# 17_FPGA_B12_B13_B14_B15.net
KiCad netlist of a schematic drawn in Altium Designer
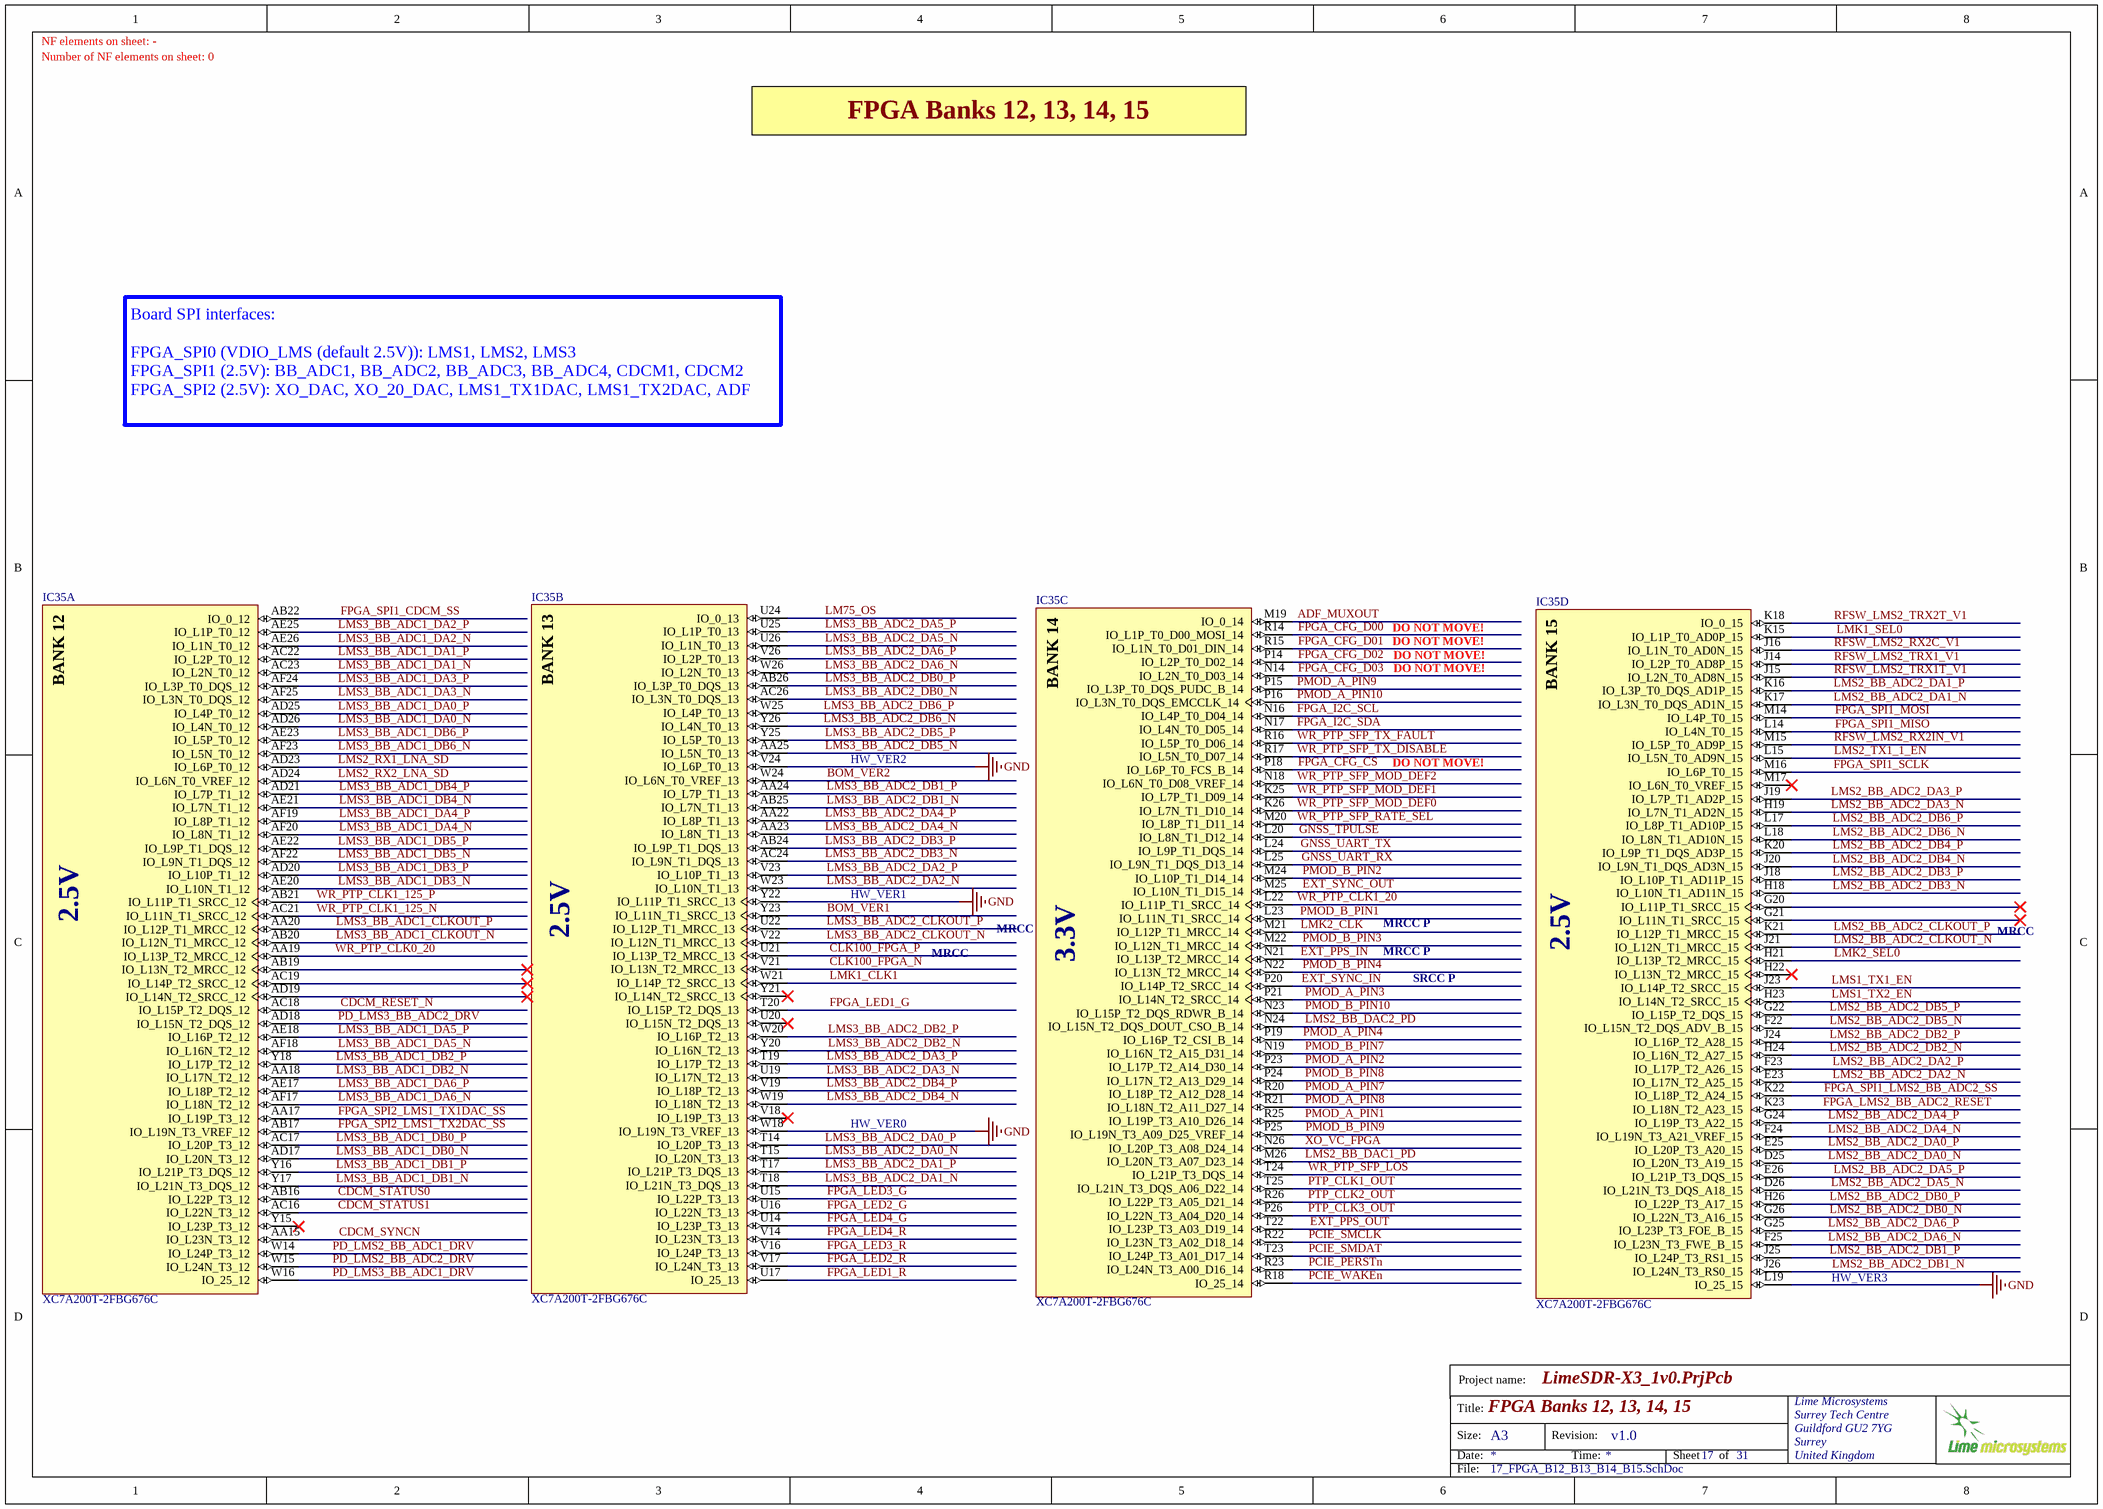
[diagram p0: 17_FPGA_B12_B13_B14_B15.SchDoc]

(export (version "E")
  (design (tool "Eeschema 10.0.6"))
  (components
    (comp (ref "IC35")
      (value "XC7A200T-2FBG676C")
      (footprint "XC7A200T-2FBG676C_FBG676")
      (description "Artix-7 FPGA, 400 User I/Os, 8 GTP, 676-Ball BGA, Speed Grade 2, Commercial Grade, Pb-Free")
      (fields (field (name "MANUFACTURER") "Xilinx"))
      (libsource (lib "") (part "XC7A200T-2FBG676C_2"))
    )
  )
  (nets
    (net (code "1") (name "/ADF_MUXOUT") (class "Default")
      (node (ref "IC35") (pin "M19") (pinfunction "IO_0_14_M19") (pintype "bidirectional"))
    )
    (net (code "2") (name "/BOM_VER1") (class "Default")
      (node (ref "IC35") (pin "Y23") (pinfunction "IO_L11N_T1_SRCC_13_Y23") (pintype "bidirectional"))
    )
    (net (code "3") (name "/BOM_VER2") (class "Default")
      (node (ref "IC35") (pin "W24") (pinfunction "IO_L6N_T0_VREF_13_W24") (pintype "bidirectional"))
    )
    (net (code "4") (name "/CDCM_RESET_N") (class "Default")
      (node (ref "IC35") (pin "AC18") (pinfunction "IO_L15P_T2_DQS_12_AC18") (pintype "bidirectional"))
    )
    (net (code "5") (name "/CDCM_STATUS0") (class "Default")
      (node (ref "IC35") (pin "AB16") (pinfunction "IO_L22P_T3_12_AB16") (pintype "bidirectional"))
    )
    (net (code "6") (name "/CDCM_STATUS1") (class "Default")
      (node (ref "IC35") (pin "AC16") (pinfunction "IO_L22N_T3_12_AC16") (pintype "bidirectional"))
    )
    (net (code "7") (name "/CDCM_SYNCN") (class "Default")
      (node (ref "IC35") (pin "AA15") (pinfunction "IO_L23N_T3_12_AA15") (pintype "bidirectional"))
    )
    (net (code "8") (name "/CLK100_FPGA_N") (class "Default")
      (node (ref "IC35") (pin "V21") (pinfunction "IO_L13N_T2_MRCC_13_V21") (pintype "bidirectional"))
    )
    (net (code "9") (name "/CLK100_FPGA_P") (class "Default")
      (node (ref "IC35") (pin "U21") (pinfunction "IO_L13P_T2_MRCC_13_U21") (pintype "bidirectional"))
    )
    (net (code "10") (name "/EXT_PPS_IN") (class "Default")
      (node (ref "IC35") (pin "N21") (pinfunction "IO_L13P_T2_MRCC_14_N21") (pintype "bidirectional"))
    )
    (net (code "11") (name "/EXT_PPS_OUT") (class "Default")
      (node (ref "IC35") (pin "T22") (pinfunction "IO_L23P_T3_A03_D19_14_T22") (pintype "bidirectional"))
    )
    (net (code "12") (name "/EXT_SYNC_IN") (class "Default")
      (node (ref "IC35") (pin "P20") (pinfunction "IO_L14P_T2_SRCC_14_P20") (pintype "bidirectional"))
    )
    (net (code "13") (name "/EXT_SYNC_OUT") (class "Default")
      (node (ref "IC35") (pin "M25") (pinfunction "IO_L10N_T1_D15_14_M25") (pintype "bidirectional"))
    )
    (net (code "14") (name "/FPGA_CFG_CS") (class "Default")
      (node (ref "IC35") (pin "P18") (pinfunction "IO_L6P_T0_FCS_B_14_P18") (pintype "bidirectional"))
    )
    (net (code "15") (name "/FPGA_CFG_D00") (class "Default")
      (node (ref "IC35") (pin "R14") (pinfunction "IO_L1P_T0_D00_MOSI_14_R14") (pintype "bidirectional"))
    )
    (net (code "16") (name "/FPGA_CFG_D01") (class "Default")
      (node (ref "IC35") (pin "R15") (pinfunction "IO_L1N_T0_D01_DIN_14_R15") (pintype "bidirectional"))
    )
    (net (code "17") (name "/FPGA_CFG_D02") (class "Default")
      (node (ref "IC35") (pin "P14") (pinfunction "IO_L2P_T0_D02_14_P14") (pintype "bidirectional"))
    )
    (net (code "18") (name "/FPGA_CFG_D03") (class "Default")
      (node (ref "IC35") (pin "N14") (pinfunction "IO_L2N_T0_D03_14_N14") (pintype "bidirectional"))
    )
    (net (code "19") (name "/FPGA_I2C_SCL") (class "Default")
      (node (ref "IC35") (pin "N16") (pinfunction "IO_L4P_T0_D04_14_N16") (pintype "bidirectional"))
    )
    (net (code "20") (name "/FPGA_I2C_SDA") (class "Default")
      (node (ref "IC35") (pin "N17") (pinfunction "IO_L4N_T0_D05_14_N17") (pintype "bidirectional"))
    )
    (net (code "21") (name "/FPGA_LED1_G") (class "Default")
      (node (ref "IC35") (pin "T20") (pinfunction "IO_L15P_T2_DQS_13_T20") (pintype "bidirectional"))
    )
    (net (code "22") (name "/FPGA_LED1_R") (class "Default")
      (node (ref "IC35") (pin "U17") (pinfunction "IO_25_13_U17") (pintype "bidirectional"))
    )
    (net (code "23") (name "/FPGA_LED2_G") (class "Default")
      (node (ref "IC35") (pin "U16") (pinfunction "IO_L22N_T3_13_U16") (pintype "bidirectional"))
    )
    (net (code "24") (name "/FPGA_LED2_R") (class "Default")
      (node (ref "IC35") (pin "V17") (pinfunction "IO_L24N_T3_13_V17") (pintype "bidirectional"))
    )
    (net (code "25") (name "/FPGA_LED3_G") (class "Default")
      (node (ref "IC35") (pin "U15") (pinfunction "IO_L22P_T3_13_U15") (pintype "bidirectional"))
    )
    (net (code "26") (name "/FPGA_LED3_R") (class "Default")
      (node (ref "IC35") (pin "V16") (pinfunction "IO_L24P_T3_13_V16") (pintype "bidirectional"))
    )
    (net (code "27") (name "/FPGA_LED4_G") (class "Default")
      (node (ref "IC35") (pin "U14") (pinfunction "IO_L23P_T3_13_U14") (pintype "bidirectional"))
    )
    (net (code "28") (name "/FPGA_LED4_R") (class "Default")
      (node (ref "IC35") (pin "V14") (pinfunction "IO_L23N_T3_13_V14") (pintype "bidirectional"))
    )
    (net (code "29") (name "/FPGA_LMS2_BB_ADC2_RESET") (class "Default")
      (node (ref "IC35") (pin "K23") (pinfunction "IO_L18N_T2_A23_15_K23") (pintype "bidirectional"))
    )
    (net (code "30") (name "/FPGA_SPI1_CDCM_SS") (class "Default")
      (node (ref "IC35") (pin "AB22") (pinfunction "IO_0_12_AB22") (pintype "bidirectional"))
    )
    (net (code "31") (name "/FPGA_SPI1_LMS2_BB_ADC2_SS") (class "Default")
      (node (ref "IC35") (pin "K22") (pinfunction "IO_L18P_T2_A24_15_K22") (pintype "bidirectional"))
    )
    (net (code "32") (name "/FPGA_SPI1_MISO") (class "Default")
      (node (ref "IC35") (pin "L14") (pinfunction "IO_L4N_T0_15_L14") (pintype "bidirectional"))
    )
    (net (code "33") (name "/FPGA_SPI1_MOSI") (class "Default")
      (node (ref "IC35") (pin "M14") (pinfunction "IO_L4P_T0_15_M14") (pintype "bidirectional"))
    )
    (net (code "34") (name "/FPGA_SPI1_SCLK") (class "Default")
      (node (ref "IC35") (pin "M16") (pinfunction "IO_L6P_T0_15_M16") (pintype "bidirectional"))
    )
    (net (code "35") (name "/FPGA_SPI2_LMS1_TX1DAC_SS") (class "Default")
      (node (ref "IC35") (pin "AA17") (pinfunction "IO_L19P_T3_12_AA17") (pintype "bidirectional"))
    )
    (net (code "36") (name "/FPGA_SPI2_LMS1_TX2DAC_SS") (class "Default")
      (node (ref "IC35") (pin "AB17") (pinfunction "IO_L19N_T3_VREF_12_AB17") (pintype "bidirectional"))
    )
    (net (code "37") (name "/GNSS_TPULSE") (class "Default")
      (node (ref "IC35") (pin "L20") (pinfunction "IO_L8N_T1_D12_14_L20") (pintype "bidirectional"))
    )
    (net (code "38") (name "/GNSS_UART_RX") (class "Default")
      (node (ref "IC35") (pin "L25") (pinfunction "IO_L9N_T1_DQS_D13_14_L25") (pintype "bidirectional"))
    )
    (net (code "39") (name "/GNSS_UART_TX") (class "Default")
      (node (ref "IC35") (pin "L24") (pinfunction "IO_L9P_T1_DQS_14_L24") (pintype "bidirectional"))
    )
    (net (code "40") (name "/LM75_OS") (class "Default")
      (node (ref "IC35") (pin "U24") (pinfunction "IO_0_13_U24") (pintype "bidirectional"))
    )
    (net (code "41") (name "/LMK1_CLK1") (class "Default")
      (node (ref "IC35") (pin "W21") (pinfunction "IO_L14P_T2_SRCC_13_W21") (pintype "bidirectional"))
    )
    (net (code "42") (name "/LMK1_SEL0") (class "Default")
      (node (ref "IC35") (pin "K15") (pinfunction "IO_L1P_T0_AD0P_15_K15") (pintype "bidirectional"))
    )
    (net (code "43") (name "/LMK2_CLK") (class "Default")
      (node (ref "IC35") (pin "M21") (pinfunction "IO_L12P_T1_MRCC_14_M21") (pintype "bidirectional"))
    )
    (net (code "44") (name "/LMK2_SEL0") (class "Default")
      (node (ref "IC35") (pin "H21") (pinfunction "IO_L13P_T2_MRCC_15_H21") (pintype "bidirectional"))
    )
    (net (code "45") (name "/LMS1_TX1_EN") (class "Default")
      (node (ref "IC35") (pin "J23") (pinfunction "IO_L14P_T2_SRCC_15_J23") (pintype "bidirectional"))
    )
    (net (code "46") (name "/LMS1_TX2_EN") (class "Default")
      (node (ref "IC35") (pin "H23") (pinfunction "IO_L14N_T2_SRCC_15_H23") (pintype "bidirectional"))
    )
    (net (code "47") (name "/LMS2_BB_ADC2_CLKOUT_N") (class "Default")
      (node (ref "IC35") (pin "J21") (pinfunction "IO_L12N_T1_MRCC_15_J21") (pintype "bidirectional"))
    )
    (net (code "48") (name "/LMS2_BB_ADC2_CLKOUT_P") (class "Default")
      (node (ref "IC35") (pin "K21") (pinfunction "IO_L12P_T1_MRCC_15_K21") (pintype "bidirectional"))
    )
    (net (code "49") (name "/LMS2_BB_ADC2_DA0_N") (class "Default")
      (node (ref "IC35") (pin "D25") (pinfunction "IO_L20N_T3_A19_15_D25") (pintype "bidirectional"))
    )
    (net (code "50") (name "/LMS2_BB_ADC2_DA0_P") (class "Default")
      (node (ref "IC35") (pin "E25") (pinfunction "IO_L20P_T3_A20_15_E25") (pintype "bidirectional"))
    )
    (net (code "51") (name "/LMS2_BB_ADC2_DA1_N") (class "Default")
      (node (ref "IC35") (pin "K17") (pinfunction "IO_L3N_T0_DQS_AD1N_15_K17") (pintype "bidirectional"))
    )
    (net (code "52") (name "/LMS2_BB_ADC2_DA1_P") (class "Default")
      (node (ref "IC35") (pin "K16") (pinfunction "IO_L3P_T0_DQS_AD1P_15_K16") (pintype "bidirectional"))
    )
    (net (code "53") (name "/LMS2_BB_ADC2_DA2_N") (class "Default")
      (node (ref "IC35") (pin "E23") (pinfunction "IO_L17N_T2_A25_15_E23") (pintype "bidirectional"))
    )
    (net (code "54") (name "/LMS2_BB_ADC2_DA2_P") (class "Default")
      (node (ref "IC35") (pin "F23") (pinfunction "IO_L17P_T2_A26_15_F23") (pintype "bidirectional"))
    )
    (net (code "55") (name "/LMS2_BB_ADC2_DA3_N") (class "Default")
      (node (ref "IC35") (pin "H19") (pinfunction "IO_L7N_T1_AD2N_15_H19") (pintype "bidirectional"))
    )
    (net (code "56") (name "/LMS2_BB_ADC2_DA3_P") (class "Default")
      (node (ref "IC35") (pin "J19") (pinfunction "IO_L7P_T1_AD2P_15_J19") (pintype "bidirectional"))
    )
    (net (code "57") (name "/LMS2_BB_ADC2_DA4_N") (class "Default")
      (node (ref "IC35") (pin "F24") (pinfunction "IO_L19N_T3_A21_VREF_15_F24") (pintype "bidirectional"))
    )
    (net (code "58") (name "/LMS2_BB_ADC2_DA4_P") (class "Default")
      (node (ref "IC35") (pin "G24") (pinfunction "IO_L19P_T3_A22_15_G24") (pintype "bidirectional"))
    )
    (net (code "59") (name "/LMS2_BB_ADC2_DA5_N") (class "Default")
      (node (ref "IC35") (pin "D26") (pinfunction "IO_L21N_T3_DQS_A18_15_D26") (pintype "bidirectional"))
    )
    (net (code "60") (name "/LMS2_BB_ADC2_DA5_P") (class "Default")
      (node (ref "IC35") (pin "E26") (pinfunction "IO_L21P_T3_DQS_15_E26") (pintype "bidirectional"))
    )
    (net (code "61") (name "/LMS2_BB_ADC2_DA6_N") (class "Default")
      (node (ref "IC35") (pin "F25") (pinfunction "IO_L23N_T3_FWE_B_15_F25") (pintype "bidirectional"))
    )
    (net (code "62") (name "/LMS2_BB_ADC2_DA6_P") (class "Default")
      (node (ref "IC35") (pin "G25") (pinfunction "IO_L23P_T3_FOE_B_15_G25") (pintype "bidirectional"))
    )
    (net (code "63") (name "/LMS2_BB_ADC2_DB0_N") (class "Default")
      (node (ref "IC35") (pin "G26") (pinfunction "IO_L22N_T3_A16_15_G26") (pintype "bidirectional"))
    )
    (net (code "64") (name "/LMS2_BB_ADC2_DB0_P") (class "Default")
      (node (ref "IC35") (pin "H26") (pinfunction "IO_L22P_T3_A17_15_H26") (pintype "bidirectional"))
    )
    (net (code "65") (name "/LMS2_BB_ADC2_DB1_N") (class "Default")
      (node (ref "IC35") (pin "J26") (pinfunction "IO_L24N_T3_RS0_15_J26") (pintype "bidirectional"))
    )
    (net (code "66") (name "/LMS2_BB_ADC2_DB1_P") (class "Default")
      (node (ref "IC35") (pin "J25") (pinfunction "IO_L24P_T3_RS1_15_J25") (pintype "bidirectional"))
    )
    (net (code "67") (name "/LMS2_BB_ADC2_DB2_N") (class "Default")
      (node (ref "IC35") (pin "H24") (pinfunction "IO_L16N_T2_A27_15_H24") (pintype "bidirectional"))
    )
    (net (code "68") (name "/LMS2_BB_ADC2_DB2_P") (class "Default")
      (node (ref "IC35") (pin "J24") (pinfunction "IO_L16P_T2_A28_15_J24") (pintype "bidirectional"))
    )
    (net (code "69") (name "/LMS2_BB_ADC2_DB3_N") (class "Default")
      (node (ref "IC35") (pin "H18") (pinfunction "IO_L10N_T1_AD11N_15_H18") (pintype "bidirectional"))
    )
    (net (code "70") (name "/LMS2_BB_ADC2_DB3_P") (class "Default")
      (node (ref "IC35") (pin "J18") (pinfunction "IO_L10P_T1_AD11P_15_J18") (pintype "bidirectional"))
    )
    (net (code "71") (name "/LMS2_BB_ADC2_DB4_N") (class "Default")
      (node (ref "IC35") (pin "J20") (pinfunction "IO_L9N_T1_DQS_AD3N_15_J20") (pintype "bidirectional"))
    )
    (net (code "72") (name "/LMS2_BB_ADC2_DB4_P") (class "Default")
      (node (ref "IC35") (pin "K20") (pinfunction "IO_L9P_T1_DQS_AD3P_15_K20") (pintype "bidirectional"))
    )
    (net (code "73") (name "/LMS2_BB_ADC2_DB5_N") (class "Default")
      (node (ref "IC35") (pin "F22") (pinfunction "IO_L15N_T2_DQS_ADV_B_15_F22") (pintype "bidirectional"))
    )
    (net (code "74") (name "/LMS2_BB_ADC2_DB5_P") (class "Default")
      (node (ref "IC35") (pin "G22") (pinfunction "IO_L15P_T2_DQS_15_G22") (pintype "bidirectional"))
    )
    (net (code "75") (name "/LMS2_BB_ADC2_DB6_N") (class "Default")
      (node (ref "IC35") (pin "L18") (pinfunction "IO_L8N_T1_AD10N_15_L18") (pintype "bidirectional"))
    )
    (net (code "76") (name "/LMS2_BB_ADC2_DB6_P") (class "Default")
      (node (ref "IC35") (pin "L17") (pinfunction "IO_L8P_T1_AD10P_15_L17") (pintype "bidirectional"))
    )
    (net (code "77") (name "/LMS2_BB_DAC1_PD") (class "Default")
      (node (ref "IC35") (pin "M26") (pinfunction "IO_L20N_T3_A07_D23_14_M26") (pintype "bidirectional"))
    )
    (net (code "78") (name "/LMS2_BB_DAC2_PD") (class "Default")
      (node (ref "IC35") (pin "N24") (pinfunction "IO_L15N_T2_DQS_DOUT_CSO_B_14_N24") (pintype "bidirectional"))
    )
    (net (code "79") (name "/LMS2_RX1_LNA_SD") (class "Default")
      (node (ref "IC35") (pin "AD23") (pinfunction "IO_L6P_T0_12_AD23") (pintype "bidirectional"))
    )
    (net (code "80") (name "/LMS2_RX2_LNA_SD") (class "Default")
      (node (ref "IC35") (pin "AD24") (pinfunction "IO_L6N_T0_VREF_12_AD24") (pintype "bidirectional"))
    )
    (net (code "81") (name "/LMS2_TX1_1_EN") (class "Default")
      (node (ref "IC35") (pin "L15") (pinfunction "IO_L5N_T0_AD9N_15_L15") (pintype "bidirectional"))
    )
    (net (code "82") (name "/LMS3_BB_ADC1_CLKOUT_N") (class "Default")
      (node (ref "IC35") (pin "AB20") (pinfunction "IO_L12N_T1_MRCC_12_AB20") (pintype "bidirectional"))
    )
    (net (code "83") (name "/LMS3_BB_ADC1_CLKOUT_P") (class "Default")
      (node (ref "IC35") (pin "AA20") (pinfunction "IO_L12P_T1_MRCC_12_AA20") (pintype "bidirectional"))
    )
    (net (code "84") (name "/LMS3_BB_ADC1_DA0_N") (class "Default")
      (node (ref "IC35") (pin "AD26") (pinfunction "IO_L4N_T0_12_AD26") (pintype "bidirectional"))
    )
    (net (code "85") (name "/LMS3_BB_ADC1_DA0_P") (class "Default")
      (node (ref "IC35") (pin "AD25") (pinfunction "IO_L4P_T0_12_AD25") (pintype "bidirectional"))
    )
    (net (code "86") (name "/LMS3_BB_ADC1_DA1_N") (class "Default")
      (node (ref "IC35") (pin "AC23") (pinfunction "IO_L2N_T0_12_AC23") (pintype "bidirectional"))
    )
    (net (code "87") (name "/LMS3_BB_ADC1_DA1_P") (class "Default")
      (node (ref "IC35") (pin "AC22") (pinfunction "IO_L2P_T0_12_AC22") (pintype "bidirectional"))
    )
    (net (code "88") (name "/LMS3_BB_ADC1_DA2_N") (class "Default")
      (node (ref "IC35") (pin "AE26") (pinfunction "IO_L1N_T0_12_AE26") (pintype "bidirectional"))
    )
    (net (code "89") (name "/LMS3_BB_ADC1_DA2_P") (class "Default")
      (node (ref "IC35") (pin "AE25") (pinfunction "IO_L1P_T0_12_AE25") (pintype "bidirectional"))
    )
    (net (code "90") (name "/LMS3_BB_ADC1_DA3_N") (class "Default")
      (node (ref "IC35") (pin "AF25") (pinfunction "IO_L3N_T0_DQS_12_AF25") (pintype "bidirectional"))
    )
    (net (code "91") (name "/LMS3_BB_ADC1_DA3_P") (class "Default")
      (node (ref "IC35") (pin "AF24") (pinfunction "IO_L3P_T0_DQS_12_AF24") (pintype "bidirectional"))
    )
    (net (code "92") (name "/LMS3_BB_ADC1_DA4_N") (class "Default")
      (node (ref "IC35") (pin "AF20") (pinfunction "IO_L8N_T1_12_AF20") (pintype "bidirectional"))
    )
    (net (code "93") (name "/LMS3_BB_ADC1_DA4_P") (class "Default")
      (node (ref "IC35") (pin "AF19") (pinfunction "IO_L8P_T1_12_AF19") (pintype "bidirectional"))
    )
    (net (code "94") (name "/LMS3_BB_ADC1_DA5_N") (class "Default")
      (node (ref "IC35") (pin "AF18") (pinfunction "IO_L16N_T2_12_AF18") (pintype "bidirectional"))
    )
    (net (code "95") (name "/LMS3_BB_ADC1_DA5_P") (class "Default")
      (node (ref "IC35") (pin "AE18") (pinfunction "IO_L16P_T2_12_AE18") (pintype "bidirectional"))
    )
    (net (code "96") (name "/LMS3_BB_ADC1_DA6_N") (class "Default")
      (node (ref "IC35") (pin "AF17") (pinfunction "IO_L18N_T2_12_AF17") (pintype "bidirectional"))
    )
    (net (code "97") (name "/LMS3_BB_ADC1_DA6_P") (class "Default")
      (node (ref "IC35") (pin "AE17") (pinfunction "IO_L18P_T2_12_AE17") (pintype "bidirectional"))
    )
    (net (code "98") (name "/LMS3_BB_ADC1_DB0_N") (class "Default")
      (node (ref "IC35") (pin "AD17") (pinfunction "IO_L20N_T3_12_AD17") (pintype "bidirectional"))
    )
    (net (code "99") (name "/LMS3_BB_ADC1_DB0_P") (class "Default")
      (node (ref "IC35") (pin "AC17") (pinfunction "IO_L20P_T3_12_AC17") (pintype "bidirectional"))
    )
    (net (code "100") (name "/LMS3_BB_ADC1_DB1_N") (class "Default")
      (node (ref "IC35") (pin "Y17") (pinfunction "IO_L21N_T3_DQS_12_Y17") (pintype "bidirectional"))
    )
    (net (code "101") (name "/LMS3_BB_ADC1_DB1_P") (class "Default")
      (node (ref "IC35") (pin "Y16") (pinfunction "IO_L21P_T3_DQS_12_Y16") (pintype "bidirectional"))
    )
    (net (code "102") (name "/LMS3_BB_ADC1_DB2_N") (class "Default")
      (node (ref "IC35") (pin "AA18") (pinfunction "IO_L17N_T2_12_AA18") (pintype "bidirectional"))
    )
    (net (code "103") (name "/LMS3_BB_ADC1_DB2_P") (class "Default")
      (node (ref "IC35") (pin "Y18") (pinfunction "IO_L17P_T2_12_Y18") (pintype "bidirectional"))
    )
    (net (code "104") (name "/LMS3_BB_ADC1_DB3_N") (class "Default")
      (node (ref "IC35") (pin "AE20") (pinfunction "IO_L10N_T1_12_AE20") (pintype "bidirectional"))
    )
    (net (code "105") (name "/LMS3_BB_ADC1_DB3_P") (class "Default")
      (node (ref "IC35") (pin "AD20") (pinfunction "IO_L10P_T1_12_AD20") (pintype "bidirectional"))
    )
    (net (code "106") (name "/LMS3_BB_ADC1_DB4_N") (class "Default")
      (node (ref "IC35") (pin "AE21") (pinfunction "IO_L7N_T1_12_AE21") (pintype "bidirectional"))
    )
    (net (code "107") (name "/LMS3_BB_ADC1_DB4_P") (class "Default")
      (node (ref "IC35") (pin "AD21") (pinfunction "IO_L7P_T1_12_AD21") (pintype "bidirectional"))
    )
    (net (code "108") (name "/LMS3_BB_ADC1_DB5_N") (class "Default")
      (node (ref "IC35") (pin "AF22") (pinfunction "IO_L9N_T1_DQS_12_AF22") (pintype "bidirectional"))
    )
    (net (code "109") (name "/LMS3_BB_ADC1_DB5_P") (class "Default")
      (node (ref "IC35") (pin "AE22") (pinfunction "IO_L9P_T1_DQS_12_AE22") (pintype "bidirectional"))
    )
    (net (code "110") (name "/LMS3_BB_ADC1_DB6_N") (class "Default")
      (node (ref "IC35") (pin "AF23") (pinfunction "IO_L5N_T0_12_AF23") (pintype "bidirectional"))
    )
    (net (code "111") (name "/LMS3_BB_ADC1_DB6_P") (class "Default")
      (node (ref "IC35") (pin "AE23") (pinfunction "IO_L5P_T0_12_AE23") (pintype "bidirectional"))
    )
    (net (code "112") (name "/LMS3_BB_ADC2_CLKOUT_N") (class "Default")
      (node (ref "IC35") (pin "V22") (pinfunction "IO_L12N_T1_MRCC_13_V22") (pintype "bidirectional"))
    )
    (net (code "113") (name "/LMS3_BB_ADC2_CLKOUT_P") (class "Default")
      (node (ref "IC35") (pin "U22") (pinfunction "IO_L12P_T1_MRCC_13_U22") (pintype "bidirectional"))
    )
    (net (code "114") (name "/LMS3_BB_ADC2_DA0_N") (class "Default")
      (node (ref "IC35") (pin "T15") (pinfunction "IO_L20N_T3_13_T15") (pintype "bidirectional"))
    )
    (net (code "115") (name "/LMS3_BB_ADC2_DA0_P") (class "Default")
      (node (ref "IC35") (pin "T14") (pinfunction "IO_L20P_T3_13_T14") (pintype "bidirectional"))
    )
    (net (code "116") (name "/LMS3_BB_ADC2_DA1_N") (class "Default")
      (node (ref "IC35") (pin "T18") (pinfunction "IO_L21N_T3_DQS_13_T18") (pintype "bidirectional"))
    )
    (net (code "117") (name "/LMS3_BB_ADC2_DA1_P") (class "Default")
      (node (ref "IC35") (pin "T17") (pinfunction "IO_L21P_T3_DQS_13_T17") (pintype "bidirectional"))
    )
    (net (code "118") (name "/LMS3_BB_ADC2_DA2_N") (class "Default")
      (node (ref "IC35") (pin "W23") (pinfunction "IO_L10N_T1_13_W23") (pintype "bidirectional"))
    )
    (net (code "119") (name "/LMS3_BB_ADC2_DA2_P") (class "Default")
      (node (ref "IC35") (pin "V23") (pinfunction "IO_L10P_T1_13_V23") (pintype "bidirectional"))
    )
    (net (code "120") (name "/LMS3_BB_ADC2_DA3_N") (class "Default")
      (node (ref "IC35") (pin "U19") (pinfunction "IO_L17N_T2_13_U19") (pintype "bidirectional"))
    )
    (net (code "121") (name "/LMS3_BB_ADC2_DA3_P") (class "Default")
      (node (ref "IC35") (pin "T19") (pinfunction "IO_L17P_T2_13_T19") (pintype "bidirectional"))
    )
    (net (code "122") (name "/LMS3_BB_ADC2_DA4_N") (class "Default")
      (node (ref "IC35") (pin "AA23") (pinfunction "IO_L8N_T1_13_AA23") (pintype "bidirectional"))
    )
    (net (code "123") (name "/LMS3_BB_ADC2_DA4_P") (class "Default")
      (node (ref "IC35") (pin "AA22") (pinfunction "IO_L8P_T1_13_AA22") (pintype "bidirectional"))
    )
    (net (code "124") (name "/LMS3_BB_ADC2_DA5_N") (class "Default")
      (node (ref "IC35") (pin "U26") (pinfunction "IO_L1N_T0_13_U26") (pintype "bidirectional"))
    )
    (net (code "125") (name "/LMS3_BB_ADC2_DA5_P") (class "Default")
      (node (ref "IC35") (pin "U25") (pinfunction "IO_L1P_T0_13_U25") (pintype "bidirectional"))
    )
    (net (code "126") (name "/LMS3_BB_ADC2_DA6_N") (class "Default")
      (node (ref "IC35") (pin "W26") (pinfunction "IO_L2N_T0_13_W26") (pintype "bidirectional"))
    )
    (net (code "127") (name "/LMS3_BB_ADC2_DA6_P") (class "Default")
      (node (ref "IC35") (pin "V26") (pinfunction "IO_L2P_T0_13_V26") (pintype "bidirectional"))
    )
    (net (code "128") (name "/LMS3_BB_ADC2_DB0_N") (class "Default")
      (node (ref "IC35") (pin "AC26") (pinfunction "IO_L3N_T0_DQS_13_AC26") (pintype "bidirectional"))
    )
    (net (code "129") (name "/LMS3_BB_ADC2_DB0_P") (class "Default")
      (node (ref "IC35") (pin "AB26") (pinfunction "IO_L3P_T0_DQS_13_AB26") (pintype "bidirectional"))
    )
    (net (code "130") (name "/LMS3_BB_ADC2_DB1_N") (class "Default")
      (node (ref "IC35") (pin "AB25") (pinfunction "IO_L7N_T1_13_AB25") (pintype "bidirectional"))
    )
    (net (code "131") (name "/LMS3_BB_ADC2_DB1_P") (class "Default")
      (node (ref "IC35") (pin "AA24") (pinfunction "IO_L7P_T1_13_AA24") (pintype "bidirectional"))
    )
    (net (code "132") (name "/LMS3_BB_ADC2_DB2_N") (class "Default")
      (node (ref "IC35") (pin "Y20") (pinfunction "IO_L16N_T2_13_Y20") (pintype "bidirectional"))
    )
    (net (code "133") (name "/LMS3_BB_ADC2_DB2_P") (class "Default")
      (node (ref "IC35") (pin "W20") (pinfunction "IO_L16P_T2_13_W20") (pintype "bidirectional"))
    )
    (net (code "134") (name "/LMS3_BB_ADC2_DB3_N") (class "Default")
      (node (ref "IC35") (pin "AC24") (pinfunction "IO_L9N_T1_DQS_13_AC24") (pintype "bidirectional"))
    )
    (net (code "135") (name "/LMS3_BB_ADC2_DB3_P") (class "Default")
      (node (ref "IC35") (pin "AB24") (pinfunction "IO_L9P_T1_DQS_13_AB24") (pintype "bidirectional"))
    )
    (net (code "136") (name "/LMS3_BB_ADC2_DB4_N") (class "Default")
      (node (ref "IC35") (pin "W19") (pinfunction "IO_L18N_T2_13_W19") (pintype "bidirectional"))
    )
    (net (code "137") (name "/LMS3_BB_ADC2_DB4_P") (class "Default")
      (node (ref "IC35") (pin "V19") (pinfunction "IO_L18P_T2_13_V19") (pintype "bidirectional"))
    )
    (net (code "138") (name "/LMS3_BB_ADC2_DB5_N") (class "Default")
      (node (ref "IC35") (pin "AA25") (pinfunction "IO_L5N_T0_13_AA25") (pintype "bidirectional"))
    )
    (net (code "139") (name "/LMS3_BB_ADC2_DB5_P") (class "Default")
      (node (ref "IC35") (pin "Y25") (pinfunction "IO_L5P_T0_13_Y25") (pintype "bidirectional"))
    )
    (net (code "140") (name "/LMS3_BB_ADC2_DB6_N") (class "Default")
      (node (ref "IC35") (pin "Y26") (pinfunction "IO_L4N_T0_13_Y26") (pintype "bidirectional"))
    )
    (net (code "141") (name "/LMS3_BB_ADC2_DB6_P") (class "Default")
      (node (ref "IC35") (pin "W25") (pinfunction "IO_L4P_T0_13_W25") (pintype "bidirectional"))
    )
    (net (code "142") (name "/PCIE_PERSTn") (class "Default")
      (node (ref "IC35") (pin "R23") (pinfunction "IO_L24N_T3_A00_D16_14_R23") (pintype "bidirectional"))
    )
    (net (code "143") (name "/PCIE_SMCLK") (class "Default")
      (node (ref "IC35") (pin "R22") (pinfunction "IO_L23N_T3_A02_D18_14_R22") (pintype "bidirectional"))
    )
    (net (code "144") (name "/PCIE_SMDAT") (class "Default")
      (node (ref "IC35") (pin "T23") (pinfunction "IO_L24P_T3_A01_D17_14_T23") (pintype "bidirectional"))
    )
    (net (code "145") (name "/PCIE_WAKEn") (class "Default")
      (node (ref "IC35") (pin "R18") (pinfunction "IO_25_14_R18") (pintype "bidirectional"))
    )
    (net (code "146") (name "/PD_LMS2_BB_ADC1_DRV") (class "Default")
      (node (ref "IC35") (pin "W14") (pinfunction "IO_L24P_T3_12_W14") (pintype "bidirectional"))
    )
    (net (code "147") (name "/PD_LMS2_BB_ADC2_DRV") (class "Default")
      (node (ref "IC35") (pin "W15") (pinfunction "IO_L24N_T3_12_W15") (pintype "bidirectional"))
    )
    (net (code "148") (name "/PD_LMS3_BB_ADC1_DRV") (class "Default")
      (node (ref "IC35") (pin "W16") (pinfunction "IO_25_12_W16") (pintype "bidirectional"))
    )
    (net (code "149") (name "/PD_LMS3_BB_ADC2_DRV") (class "Default")
      (node (ref "IC35") (pin "AD18") (pinfunction "IO_L15N_T2_DQS_12_AD18") (pintype "bidirectional"))
    )
    (net (code "150") (name "/PMOD_A_PIN1") (class "Default")
      (node (ref "IC35") (pin "R25") (pinfunction "IO_L19P_T3_A10_D26_14_R25") (pintype "bidirectional"))
    )
    (net (code "151") (name "/PMOD_A_PIN2") (class "Default")
      (node (ref "IC35") (pin "P23") (pinfunction "IO_L17P_T2_A14_D30_14_P23") (pintype "bidirectional"))
    )
    (net (code "152") (name "/PMOD_A_PIN3") (class "Default")
      (node (ref "IC35") (pin "P21") (pinfunction "IO_L14N_T2_SRCC_14_P21") (pintype "bidirectional"))
    )
    (net (code "153") (name "/PMOD_A_PIN4") (class "Default")
      (node (ref "IC35") (pin "P19") (pinfunction "IO_L16P_T2_CSI_B_14_P19") (pintype "bidirectional"))
    )
    (net (code "154") (name "/PMOD_A_PIN7") (class "Default")
      (node (ref "IC35") (pin "R20") (pinfunction "IO_L18P_T2_A12_D28_14_R20") (pintype "bidirectional"))
    )
    (net (code "155") (name "/PMOD_A_PIN8") (class "Default")
      (node (ref "IC35") (pin "R21") (pinfunction "IO_L18N_T2_A11_D27_14_R21") (pintype "bidirectional"))
    )
    (net (code "156") (name "/PMOD_A_PIN9") (class "Default")
      (node (ref "IC35") (pin "P15") (pinfunction "IO_L3P_T0_DQS_PUDC_B_14_P15") (pintype "bidirectional"))
    )
    (net (code "157") (name "/PMOD_A_PIN10") (class "Default")
      (node (ref "IC35") (pin "P16") (pinfunction "IO_L3N_T0_DQS_EMCCLK_14_P16") (pintype "bidirectional"))
    )
    (net (code "158") (name "/PMOD_B_PIN1") (class "Default")
      (node (ref "IC35") (pin "L23") (pinfunction "IO_L11N_T1_SRCC_14_L23") (pintype "bidirectional"))
    )
    (net (code "159") (name "/PMOD_B_PIN2") (class "Default")
      (node (ref "IC35") (pin "M24") (pinfunction "IO_L10P_T1_D14_14_M24") (pintype "bidirectional"))
    )
    (net (code "160") (name "/PMOD_B_PIN3") (class "Default")
      (node (ref "IC35") (pin "M22") (pinfunction "IO_L12N_T1_MRCC_14_M22") (pintype "bidirectional"))
    )
    (net (code "161") (name "/PMOD_B_PIN4") (class "Default")
      (node (ref "IC35") (pin "N22") (pinfunction "IO_L13N_T2_MRCC_14_N22") (pintype "bidirectional"))
    )
    (net (code "162") (name "/PMOD_B_PIN7") (class "Default")
      (node (ref "IC35") (pin "N19") (pinfunction "IO_L16N_T2_A15_D31_14_N19") (pintype "bidirectional"))
    )
    (net (code "163") (name "/PMOD_B_PIN8") (class "Default")
      (node (ref "IC35") (pin "P24") (pinfunction "IO_L17N_T2_A13_D29_14_P24") (pintype "bidirectional"))
    )
    (net (code "164") (name "/PMOD_B_PIN9") (class "Default")
      (node (ref "IC35") (pin "P25") (pinfunction "IO_L19N_T3_A09_D25_VREF_14_P25") (pintype "bidirectional"))
    )
    (net (code "165") (name "/PMOD_B_PIN10") (class "Default")
      (node (ref "IC35") (pin "N23") (pinfunction "IO_L15P_T2_DQS_RDWR_B_14_N23") (pintype "bidirectional"))
    )
    (net (code "166") (name "/PTP_CLK1_OUT") (class "Default")
      (node (ref "IC35") (pin "T25") (pinfunction "IO_L21N_T3_DQS_A06_D22_14_T25") (pintype "bidirectional"))
    )
    (net (code "167") (name "/PTP_CLK2_OUT") (class "Default")
      (node (ref "IC35") (pin "R26") (pinfunction "IO_L22P_T3_A05_D21_14_R26") (pintype "bidirectional"))
    )
    (net (code "168") (name "/PTP_CLK3_OUT") (class "Default")
      (node (ref "IC35") (pin "P26") (pinfunction "IO_L22N_T3_A04_D20_14_P26") (pintype "bidirectional"))
    )
    (net (code "169") (name "/RFSW_LMS2_RX2C_V1") (class "Default")
      (node (ref "IC35") (pin "J16") (pinfunction "IO_L1N_T0_AD0N_15_J16") (pintype "bidirectional"))
    )
    (net (code "170") (name "/RFSW_LMS2_RX2IN_V1") (class "Default")
      (node (ref "IC35") (pin "M15") (pinfunction "IO_L5P_T0_AD9P_15_M15") (pintype "bidirectional"))
    )
    (net (code "171") (name "/RFSW_LMS2_TRX1T_V1") (class "Default")
      (node (ref "IC35") (pin "J15") (pinfunction "IO_L2N_T0_AD8N_15_J15") (pintype "bidirectional"))
    )
    (net (code "172") (name "/RFSW_LMS2_TRX1_V1") (class "Default")
      (node (ref "IC35") (pin "J14") (pinfunction "IO_L2P_T0_AD8P_15_J14") (pintype "bidirectional"))
    )
    (net (code "173") (name "/RFSW_LMS2_TRX2T_V1") (class "Default")
      (node (ref "IC35") (pin "K18") (pinfunction "IO_0_15_K18") (pintype "bidirectional"))
    )
    (net (code "174") (name "/WR_PTP_CLK0_20") (class "Default")
      (node (ref "IC35") (pin "AA19") (pinfunction "IO_L13P_T2_MRCC_12_AA19") (pintype "bidirectional"))
    )
    (net (code "175") (name "/WR_PTP_CLK1_20") (class "Default")
      (node (ref "IC35") (pin "L22") (pinfunction "IO_L11P_T1_SRCC_14_L22") (pintype "bidirectional"))
    )
    (net (code "176") (name "/WR_PTP_CLK1_125_N") (class "Default")
      (node (ref "IC35") (pin "AC21") (pinfunction "IO_L11N_T1_SRCC_12_AC21") (pintype "bidirectional"))
    )
    (net (code "177") (name "/WR_PTP_CLK1_125_P") (class "Default")
      (node (ref "IC35") (pin "AB21") (pinfunction "IO_L11P_T1_SRCC_12_AB21") (pintype "bidirectional"))
    )
    (net (code "178") (name "/WR_PTP_SFP_LOS") (class "Default")
      (node (ref "IC35") (pin "T24") (pinfunction "IO_L21P_T3_DQS_14_T24") (pintype "bidirectional"))
    )
    (net (code "179") (name "/WR_PTP_SFP_MOD_DEF0") (class "Default")
      (node (ref "IC35") (pin "K26") (pinfunction "IO_L7N_T1_D10_14_K26") (pintype "bidirectional"))
    )
    (net (code "180") (name "/WR_PTP_SFP_MOD_DEF1") (class "Default")
      (node (ref "IC35") (pin "K25") (pinfunction "IO_L7P_T1_D09_14_K25") (pintype "bidirectional"))
    )
    (net (code "181") (name "/WR_PTP_SFP_MOD_DEF2") (class "Default")
      (node (ref "IC35") (pin "N18") (pinfunction "IO_L6N_T0_D08_VREF_14_N18") (pintype "bidirectional"))
    )
    (net (code "182") (name "/WR_PTP_SFP_RATE_SEL") (class "Default")
      (node (ref "IC35") (pin "M20") (pinfunction "IO_L8P_T1_D11_14_M20") (pintype "bidirectional"))
    )
    (net (code "183") (name "/WR_PTP_SFP_TX_DISABLE") (class "Default")
      (node (ref "IC35") (pin "R17") (pinfunction "IO_L5N_T0_D07_14_R17") (pintype "bidirectional"))
    )
    (net (code "184") (name "/WR_PTP_SFP_TX_FAULT") (class "Default")
      (node (ref "IC35") (pin "R16") (pinfunction "IO_L5P_T0_D06_14_R16") (pintype "bidirectional"))
    )
    (net (code "185") (name "/XO_VC_FPGA") (class "Default")
      (node (ref "IC35") (pin "N26") (pinfunction "IO_L20P_T3_A08_D24_14_N26") (pintype "bidirectional"))
    )
    (net (code "186") (name "GND") (class "Default")
      (node (ref "IC35") (pin "L19") (pinfunction "IO_25_15_L19") (pintype "bidirectional"))
      (node (ref "IC35") (pin "V24") (pinfunction "IO_L6P_T0_13_V24") (pintype "bidirectional"))
      (node (ref "IC35") (pin "W18") (pinfunction "IO_L19N_T3_VREF_13_W18") (pintype "bidirectional"))
      (node (ref "IC35") (pin "Y22") (pinfunction "IO_L11P_T1_SRCC_13_Y22") (pintype "bidirectional"))
    )
    (net (code "187") (name "unconnected-(IC35A-IO_L13N_T2_MRCC_12-PadAB19)") (class "Default")
      (node (ref "IC35") (pin "AB19") (pinfunction "IO_L13N_T2_MRCC_12_AB19") (pintype "bidirectional+no_connect"))
    )
    (net (code "188") (name "unconnected-(IC35A-IO_L14N_T2_SRCC_12-PadAD19)") (class "Default")
      (node (ref "IC35") (pin "AD19") (pinfunction "IO_L14N_T2_SRCC_12_AD19") (pintype "bidirectional+no_connect"))
    )
    (net (code "189") (name "unconnected-(IC35A-IO_L14P_T2_SRCC_12-PadAC19)") (class "Default")
      (node (ref "IC35") (pin "AC19") (pinfunction "IO_L14P_T2_SRCC_12_AC19") (pintype "bidirectional+no_connect"))
    )
    (net (code "190") (name "unconnected-(IC35A-IO_L23P_T3_12-PadY15)") (class "Default")
      (node (ref "IC35") (pin "Y15") (pinfunction "IO_L23P_T3_12_Y15") (pintype "bidirectional+no_connect"))
    )
    (net (code "191") (name "unconnected-(IC35B-IO_L14N_T2_SRCC_13-PadY21)") (class "Default")
      (node (ref "IC35") (pin "Y21") (pinfunction "IO_L14N_T2_SRCC_13_Y21") (pintype "bidirectional+no_connect"))
    )
    (net (code "192") (name "unconnected-(IC35B-IO_L15N_T2_DQS_13-PadU20)") (class "Default")
      (node (ref "IC35") (pin "U20") (pinfunction "IO_L15N_T2_DQS_13_U20") (pintype "bidirectional+no_connect"))
    )
    (net (code "193") (name "unconnected-(IC35B-IO_L19P_T3_13-PadV18)") (class "Default")
      (node (ref "IC35") (pin "V18") (pinfunction "IO_L19P_T3_13_V18") (pintype "bidirectional+no_connect"))
    )
    (net (code "194") (name "unconnected-(IC35D-IO_L6N_T0_VREF_15-PadM17)") (class "Default")
      (node (ref "IC35") (pin "M17") (pinfunction "IO_L6N_T0_VREF_15_M17") (pintype "bidirectional+no_connect"))
    )
    (net (code "195") (name "unconnected-(IC35D-IO_L11N_T1_SRCC_15-PadG21)") (class "Default")
      (node (ref "IC35") (pin "G21") (pinfunction "IO_L11N_T1_SRCC_15_G21") (pintype "bidirectional+no_connect"))
    )
    (net (code "196") (name "unconnected-(IC35D-IO_L11P_T1_SRCC_15-PadG20)") (class "Default")
      (node (ref "IC35") (pin "G20") (pinfunction "IO_L11P_T1_SRCC_15_G20") (pintype "bidirectional+no_connect"))
    )
    (net (code "197") (name "unconnected-(IC35D-IO_L13N_T2_MRCC_15-PadH22)") (class "Default")
      (node (ref "IC35") (pin "H22") (pinfunction "IO_L13N_T2_MRCC_15_H22") (pintype "bidirectional+no_connect"))
    )
  )
)
